# USB_PCIE.net
KiCad netlist of a schematic drawn in Altium Designer
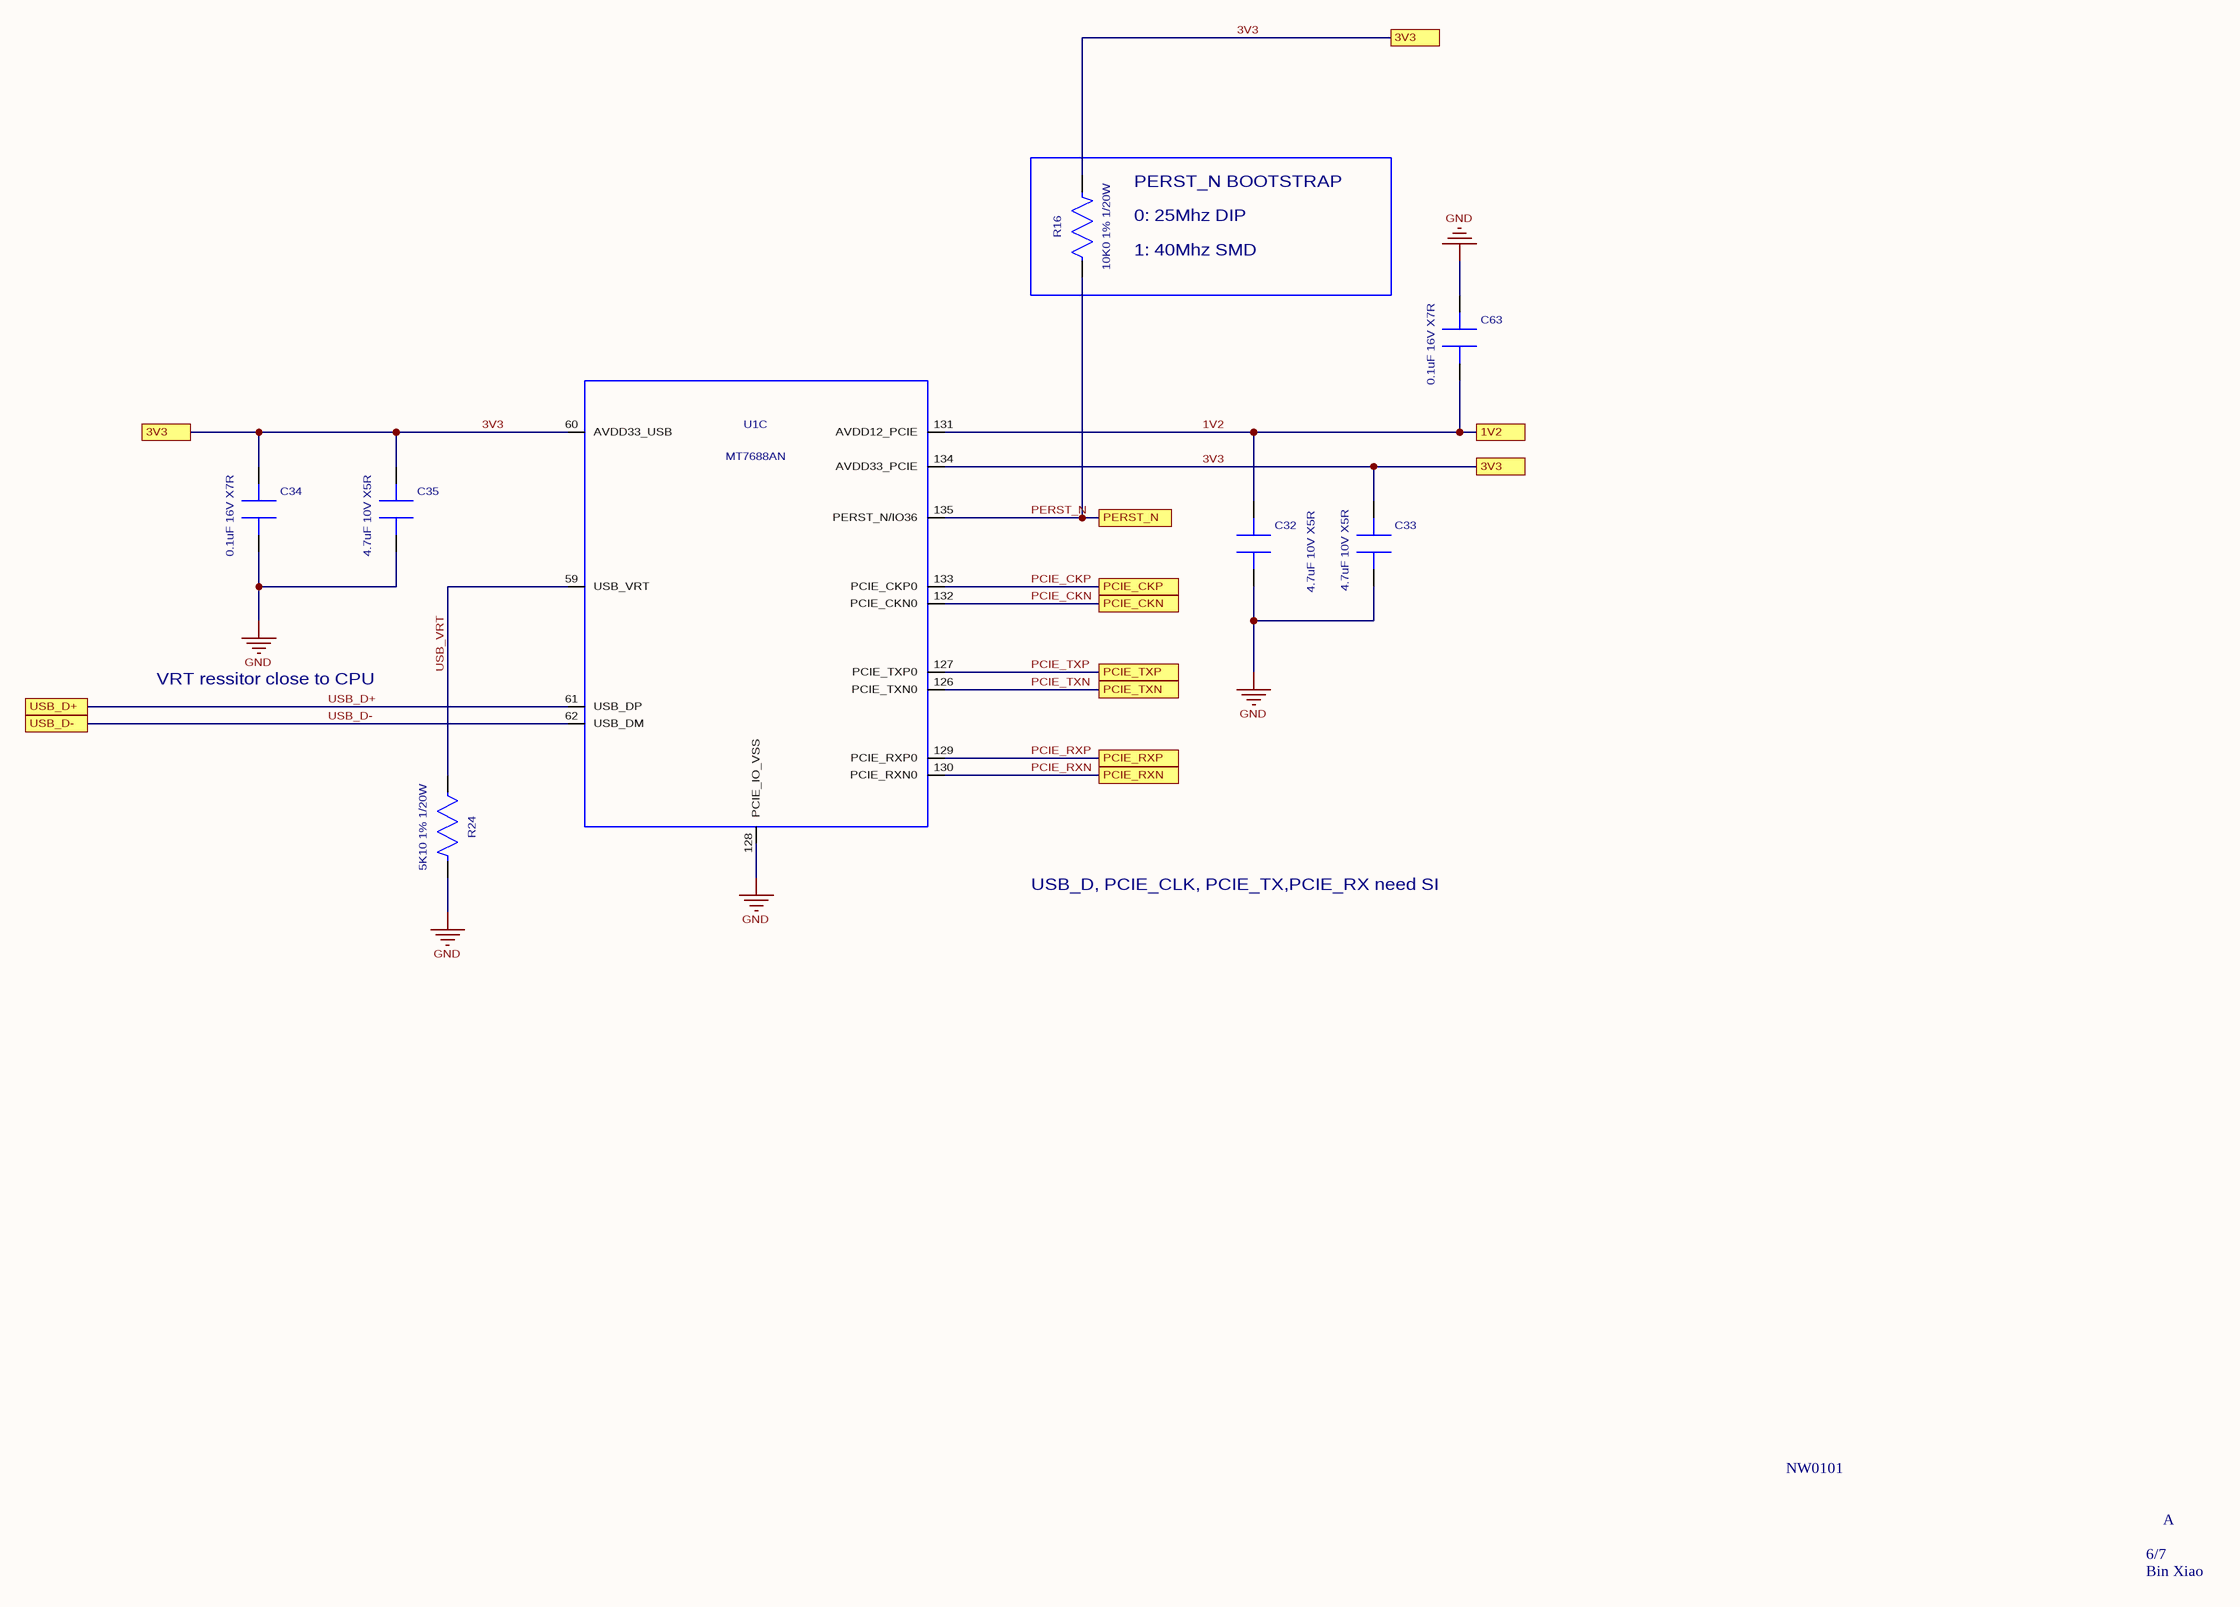
[diagram p0: USB_PCIE.SchDoc]

(export (version "E")
  (design (tool "Eeschema 10.0.6"))
  (components
    (comp (ref "C32")
      (value "4.7uF 10V X5R")
      (footprint "C0402")
      (description "CAP CER 4.7UF 10V X5R 0402")
      (fields
        (field (name "PART NUMBER") "CL05A475MP5NRNC")
        (field (name "MANUFACTURER") "Samsung Electro-Mechanics")
      )
      (libsource (lib "NetworkModule") (part "CAP0402-475-10V-X5R"))
    )
    (comp (ref "C33")
      (value "4.7uF 10V X5R")
      (footprint "C0402")
      (description "CAP CER 4.7UF 10V X5R 0402")
      (fields
        (field (name "PART NUMBER") "CL05A475MP5NRNC")
        (field (name "MANUFACTURER") "Samsung Electro-Mechanics")
      )
      (libsource (lib "NetworkModule") (part "CAP0402-475-10V-X5R"))
    )
    (comp (ref "C34")
      (value "0.1uF 16V X7R")
      (footprint "C0201")
      (description "CAP CER 0.1UF 16V X7R 0201")
      (fields
        (field (name "PART NUMBER") "GRM033Z71C104KE14D")
        (field (name "MANUFACTURER") "Murata Electronics")
      )
      (libsource (lib "NetworkModule") (part "CAP0201-104-16V-X7R"))
    )
    (comp (ref "C35")
      (value "4.7uF 10V X5R")
      (footprint "C0402")
      (description "CAP CER 4.7UF 10V X5R 0402")
      (fields
        (field (name "PART NUMBER") "CL05A475MP5NRNC")
        (field (name "MANUFACTURER") "Samsung Electro-Mechanics")
      )
      (libsource (lib "NetworkModule") (part "CAP0402-475-10V-X5R"))
    )
    (comp (ref "C63")
      (value "0.1uF 16V X7R")
      (footprint "C0201")
      (description "CAP CER 0.1UF 16V X7R 0201")
      (fields
        (field (name "PART NUMBER") "GRM033Z71C104KE14D")
        (field (name "MANUFACTURER") "Murata Electronics")
      )
      (libsource (lib "NetworkModule") (part "CAP0201-104-16V-X7R"))
    )
    (comp (ref "R16")
      (value "10K0 1% 1/20W")
      (footprint "R0201")
      (description "RES SMD 10K OHM 1% 1/20W 0201")
      (fields (field (name "MANUFACTURER") "Yageo") (field (name "PART NUMBER") "RC0201FR-0710KP"))
      (libsource (lib "NetworkModule") (part "RES0201-10K0"))
    )
    (comp (ref "R24")
      (value "5K10 1% 1/20W")
      (footprint "R0201")
      (description "RES SMD 5.1K OHM 1% 1/20W 0201")
      (fields (field (name "PART NUMBER") "AC0201FR-075K1L") (field (name "MANUFACTURER") "YAGEO"))
      (libsource (lib "NetworkModule") (part "RES0201-5K10"))
    )
    (comp (ref "U1")
      (value "MT7688AN")
      (footprint "DR-QFN-128")
      (description "580Mhz 32bits Networking Processor")
      (fields (field (name "MANUFACTURER") "MediaTek Inc"))
      (libsource (lib "*") (part "MT7688AN"))
    )
  )
  (nets
    (net (code "1") (name "/1V2") (class "Default")
      (node (ref "C32") (pin "1") (pinfunction "1_1") (pintype "passive"))
      (node (ref "C63") (pin "2") (pinfunction "2_2") (pintype "passive"))
      (node (ref "U1") (pin "131") (pinfunction "AVDD12_PCIE_131") (pintype "passive"))
    )
    (net (code "2") (name "/3V3") (class "Default")
      (node (ref "C33") (pin "1") (pinfunction "1_1") (pintype "passive"))
      (node (ref "C34") (pin "1") (pinfunction "1_1") (pintype "passive"))
      (node (ref "C35") (pin "1") (pinfunction "1_1") (pintype "passive"))
      (node (ref "R16") (pin "2") (pinfunction "2_2") (pintype "passive"))
      (node (ref "U1") (pin "134") (pinfunction "AVDD33_PCIE_134") (pintype "passive"))
      (node (ref "U1") (pin "60") (pinfunction "AVDD33_USB_60") (pintype "passive"))
    )
    (net (code "3") (name "/PCIE_CKN") (class "Default")
      (node (ref "U1") (pin "132") (pinfunction "PCIE_CKN0_132") (pintype "passive"))
    )
    (net (code "4") (name "/PCIE_CKP") (class "Default")
      (node (ref "U1") (pin "133") (pinfunction "PCIE_CKP0_133") (pintype "passive"))
    )
    (net (code "5") (name "/PCIE_RXN") (class "Default")
      (node (ref "U1") (pin "130") (pinfunction "PCIE_RXN0_130") (pintype "passive"))
    )
    (net (code "6") (name "/PCIE_RXP") (class "Default")
      (node (ref "U1") (pin "129") (pinfunction "PCIE_RXP0_129") (pintype "passive"))
    )
    (net (code "7") (name "/PCIE_TXN") (class "Default")
      (node (ref "U1") (pin "126") (pinfunction "PCIE_TXN0_126") (pintype "passive"))
    )
    (net (code "8") (name "/PCIE_TXP") (class "Default")
      (node (ref "U1") (pin "127") (pinfunction "PCIE_TXP0_127") (pintype "passive"))
    )
    (net (code "9") (name "/PERST_N") (class "Default")
      (node (ref "R16") (pin "1") (pinfunction "1_1") (pintype "passive"))
      (node (ref "U1") (pin "135") (pinfunction "PERST_N/IO36_135") (pintype "passive"))
    )
    (net (code "10") (name "/USB_D+") (class "Default")
      (node (ref "U1") (pin "61") (pinfunction "USB_DP_61") (pintype "passive"))
    )
    (net (code "11") (name "/USB_D-") (class "Default")
      (node (ref "U1") (pin "62") (pinfunction "USB_DM_62") (pintype "passive"))
    )
    (net (code "12") (name "/USB_VRT") (class "Default")
      (node (ref "R24") (pin "1") (pinfunction "1_1") (pintype "passive"))
      (node (ref "U1") (pin "59") (pinfunction "USB_VRT_59") (pintype "passive"))
    )
    (net (code "13") (name "GND") (class "Default")
      (node (ref "C32") (pin "2") (pinfunction "2_2") (pintype "passive"))
      (node (ref "C33") (pin "2") (pinfunction "2_2") (pintype "passive"))
      (node (ref "C34") (pin "2") (pinfunction "2_2") (pintype "passive"))
      (node (ref "C35") (pin "2") (pinfunction "2_2") (pintype "passive"))
      (node (ref "C63") (pin "1") (pinfunction "1_1") (pintype "passive"))
      (node (ref "R24") (pin "2") (pinfunction "2_2") (pintype "passive"))
      (node (ref "U1") (pin "128") (pinfunction "PCIE_IO_VSS_128") (pintype "passive"))
    )
  )
)
